# baza.net
KiCad netlist of a schematic drawn in EAGLE
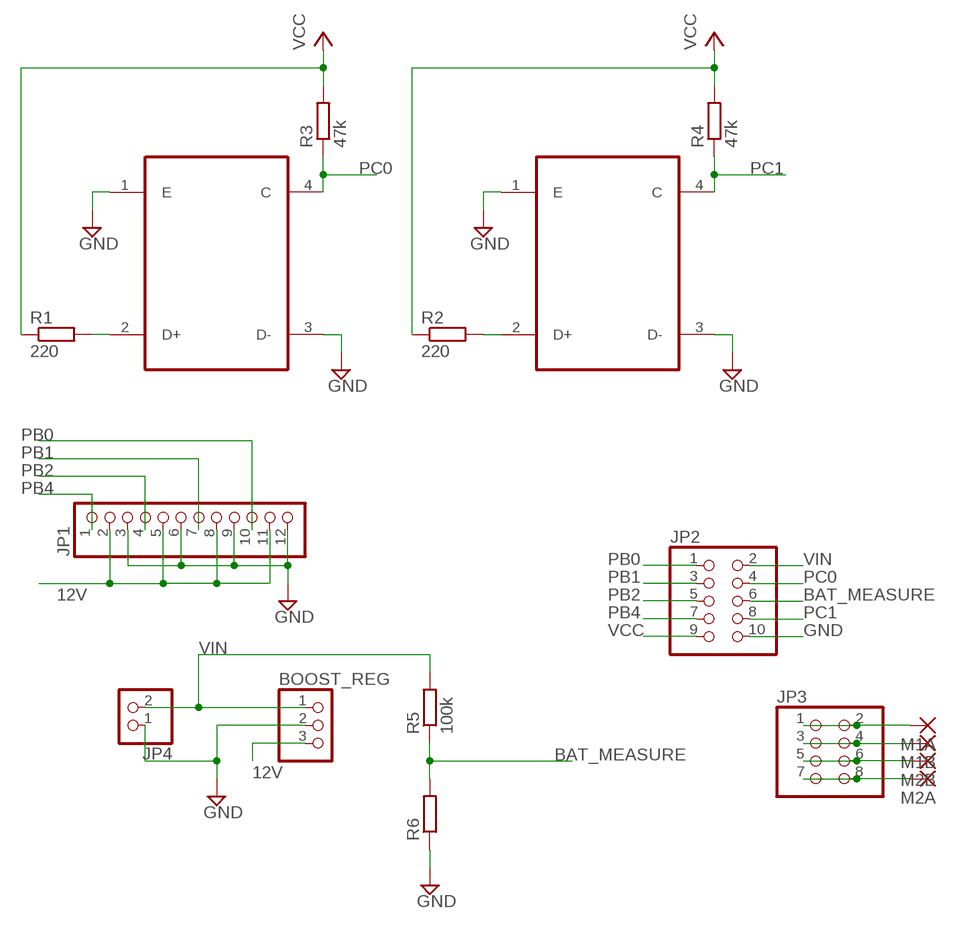
[diagram p0: schematic, sheet 1]

(export (version "E")
  (design (tool "Eeschema 10.0.6"))
  (components
    (comp (ref "BOOST_REG")
      (value "PINHD-1X3")
      (footprint "eagle-import:1X03")
      (libsource (lib "eagle-import") (part "PINHD-1X3"))
    )
    (comp (ref "IR1")
      (value "TCNT2000")
      (footprint "eagle-import:TCNT2000")
      (libsource (lib "eagle-import") (part "TCNT2000"))
    )
    (comp (ref "IR2")
      (value "TCNT2000")
      (footprint "eagle-import:TCNT2000")
      (libsource (lib "eagle-import") (part "TCNT2000"))
    )
    (comp (ref "JP1")
      (value "PINHD-1X12-CB")
      (footprint "eagle-import:1X12-CB")
      (libsource (lib "eagle-import") (part "PINHD-1X12-CB"))
    )
    (comp (ref "JP2")
      (value "PINHD-2X5")
      (footprint "eagle-import:2X05")
      (libsource (lib "eagle-import") (part "PINHD-2X5"))
    )
    (comp (ref "JP3")
      (value "PINHD-2X4")
      (footprint "eagle-import:2X04")
      (libsource (lib "eagle-import") (part "PINHD-2X4"))
    )
    (comp (ref "JP4")
      (value "PINHD-1X2")
      (footprint "eagle-import:1X02")
      (libsource (lib "eagle-import") (part "PINHD-1X2"))
    )
    (comp (ref "M1A")
      (value "2,15/1,0")
      (footprint "eagle-import:2,15_1,0")
      (libsource (lib "eagle-import") (part "2,15/1,0"))
    )
    (comp (ref "M1B")
      (value "2,15/1,0")
      (footprint "eagle-import:2,15_1,0")
      (libsource (lib "eagle-import") (part "2,15/1,0"))
    )
    (comp (ref "M2A")
      (value "2,15/1,0")
      (footprint "eagle-import:2,15_1,0")
      (libsource (lib "eagle-import") (part "2,15/1,0"))
    )
    (comp (ref "M2B")
      (value "2,15/1,0")
      (footprint "eagle-import:2,15_1,0")
      (libsource (lib "eagle-import") (part "2,15/1,0"))
    )
    (comp (ref "R1")
      (value "220")
      (footprint "eagle-import:M1206")
      (libsource (lib "eagle-import") (part "R-EU_M1206"))
    )
    (comp (ref "R2")
      (value "220")
      (footprint "eagle-import:M1206")
      (libsource (lib "eagle-import") (part "R-EU_M1206"))
    )
    (comp (ref "R3")
      (value "47k")
      (footprint "eagle-import:M1206")
      (libsource (lib "eagle-import") (part "R-EU_M1206"))
    )
    (comp (ref "R4")
      (value "47k")
      (footprint "eagle-import:M1206")
      (libsource (lib "eagle-import") (part "R-EU_M1206"))
    )
    (comp (ref "R5")
      (value "100k")
      (footprint "eagle-import:R1206")
      (libsource (lib "eagle-import") (part "R-EU_R1206"))
    )
    (comp (ref "R6")
      (value "R-EU_R1206")
      (footprint "eagle-import:R1206")
      (libsource (lib "eagle-import") (part "R-EU_R1206"))
    )
  )
  (nets
    (net (code "1") (name "/12V") (class "Default")
      (node (ref "BOOST_REG") (pin "3") (pinfunction "3_3") (pintype "passive"))
      (node (ref "JP1") (pin "11") (pinfunction "11_11") (pintype "passive"))
      (node (ref "JP1") (pin "2") (pinfunction "2_2") (pintype "passive"))
      (node (ref "JP1") (pin "5") (pinfunction "5_5") (pintype "passive"))
      (node (ref "JP1") (pin "8") (pinfunction "8_8") (pintype "passive"))
    )
    (net (code "2") (name "/BAT_MEASURE") (class "Default")
      (node (ref "JP2") (pin "6") (pinfunction "6_6") (pintype "passive"))
      (node (ref "R5") (pin "1") (pinfunction "1_1") (pintype "passive"))
      (node (ref "R6") (pin "2") (pinfunction "2_2") (pintype "passive"))
    )
    (net (code "3") (name "/PB0") (class "Default")
      (node (ref "JP1") (pin "10") (pinfunction "10_10") (pintype "passive"))
      (node (ref "JP2") (pin "1") (pinfunction "1_1") (pintype "passive"))
    )
    (net (code "4") (name "/PB1") (class "Default")
      (node (ref "JP1") (pin "7") (pinfunction "7_7") (pintype "passive"))
      (node (ref "JP2") (pin "3") (pinfunction "3_3") (pintype "passive"))
    )
    (net (code "5") (name "/PB2") (class "Default")
      (node (ref "JP1") (pin "4") (pinfunction "4_4") (pintype "passive"))
      (node (ref "JP2") (pin "5") (pinfunction "5_5") (pintype "passive"))
    )
    (net (code "6") (name "/PB4") (class "Default")
      (node (ref "JP1") (pin "1") (pinfunction "1_1") (pintype "passive"))
      (node (ref "JP2") (pin "7") (pinfunction "7_7") (pintype "passive"))
    )
    (net (code "7") (name "/PC0") (class "Default")
      (node (ref "IR1") (pin "4") (pinfunction "C_4") (pintype "bidirectional"))
      (node (ref "JP2") (pin "4") (pinfunction "4_4") (pintype "passive"))
      (node (ref "R3") (pin "1") (pinfunction "1_1") (pintype "passive"))
    )
    (net (code "8") (name "/PC1") (class "Default")
      (node (ref "IR2") (pin "4") (pinfunction "C_4") (pintype "bidirectional"))
      (node (ref "JP2") (pin "8") (pinfunction "8_8") (pintype "passive"))
      (node (ref "R4") (pin "1") (pinfunction "1_1") (pintype "passive"))
    )
    (net (code "9") (name "/VIN") (class "Default")
      (node (ref "BOOST_REG") (pin "1") (pinfunction "1_1") (pintype "passive"))
      (node (ref "JP2") (pin "2") (pinfunction "2_2") (pintype "passive"))
      (node (ref "JP4") (pin "2") (pinfunction "2_2") (pintype "passive"))
      (node (ref "R5") (pin "2") (pinfunction "2_2") (pintype "passive"))
    )
    (net (code "10") (name "GND") (class "Default")
      (node (ref "BOOST_REG") (pin "2") (pinfunction "2_2") (pintype "passive"))
      (node (ref "IR1") (pin "1") (pinfunction "E_1") (pintype "bidirectional"))
      (node (ref "IR1") (pin "3") (pinfunction "D-_3") (pintype "bidirectional"))
      (node (ref "IR2") (pin "1") (pinfunction "E_1") (pintype "bidirectional"))
      (node (ref "IR2") (pin "3") (pinfunction "D-_3") (pintype "bidirectional"))
      (node (ref "JP1") (pin "12") (pinfunction "12_12") (pintype "passive"))
      (node (ref "JP1") (pin "3") (pinfunction "3_3") (pintype "passive"))
      (node (ref "JP1") (pin "6") (pinfunction "6_6") (pintype "passive"))
      (node (ref "JP1") (pin "9") (pinfunction "9_9") (pintype "passive"))
      (node (ref "JP2") (pin "10") (pinfunction "10_10") (pintype "passive"))
      (node (ref "JP4") (pin "1") (pinfunction "1_1") (pintype "passive"))
      (node (ref "R6") (pin "1") (pinfunction "1_1") (pintype "passive"))
    )
    (net (code "11") (name "Net-(IR1-D+)") (class "Default")
      (node (ref "IR1") (pin "2") (pinfunction "D+_2") (pintype "bidirectional"))
      (node (ref "R1") (pin "2") (pinfunction "2_2") (pintype "passive"))
    )
    (net (code "12") (name "Net-(IR2-D+)") (class "Default")
      (node (ref "IR2") (pin "2") (pinfunction "D+_2") (pintype "bidirectional"))
      (node (ref "R2") (pin "2") (pinfunction "2_2") (pintype "passive"))
    )
    (net (code "13") (name "Net-(M1A-P)") (class "Default")
      (node (ref "JP3") (pin "1") (pinfunction "1_1") (pintype "passive"))
      (node (ref "JP3") (pin "2") (pinfunction "2_2") (pintype "passive"))
      (node (ref "M1A") (pin "1") (pinfunction "P_1") (pintype "passive"))
    )
    (net (code "14") (name "Net-(M1B-P)") (class "Default")
      (node (ref "JP3") (pin "3") (pinfunction "3_3") (pintype "passive"))
      (node (ref "JP3") (pin "4") (pinfunction "4_4") (pintype "passive"))
      (node (ref "M1B") (pin "1") (pinfunction "P_1") (pintype "passive"))
    )
    (net (code "15") (name "Net-(M2A-P)") (class "Default")
      (node (ref "JP3") (pin "7") (pinfunction "7_7") (pintype "passive"))
      (node (ref "JP3") (pin "8") (pinfunction "8_8") (pintype "passive"))
      (node (ref "M2A") (pin "1") (pinfunction "P_1") (pintype "passive"))
    )
    (net (code "16") (name "Net-(M2B-P)") (class "Default")
      (node (ref "JP3") (pin "5") (pinfunction "5_5") (pintype "passive"))
      (node (ref "JP3") (pin "6") (pinfunction "6_6") (pintype "passive"))
      (node (ref "M2B") (pin "1") (pinfunction "P_1") (pintype "passive"))
    )
    (net (code "17") (name "VCC") (class "Default")
      (node (ref "JP2") (pin "9") (pinfunction "9_9") (pintype "passive"))
      (node (ref "R1") (pin "1") (pinfunction "1_1") (pintype "passive"))
      (node (ref "R2") (pin "1") (pinfunction "1_1") (pintype "passive"))
      (node (ref "R3") (pin "2") (pinfunction "2_2") (pintype "passive"))
      (node (ref "R4") (pin "2") (pinfunction "2_2") (pintype "passive"))
    )
  )
)
